# 8Bit-audio-7524-axelb-v2.net
KiCad netlist of a schematic drawn in EAGLE
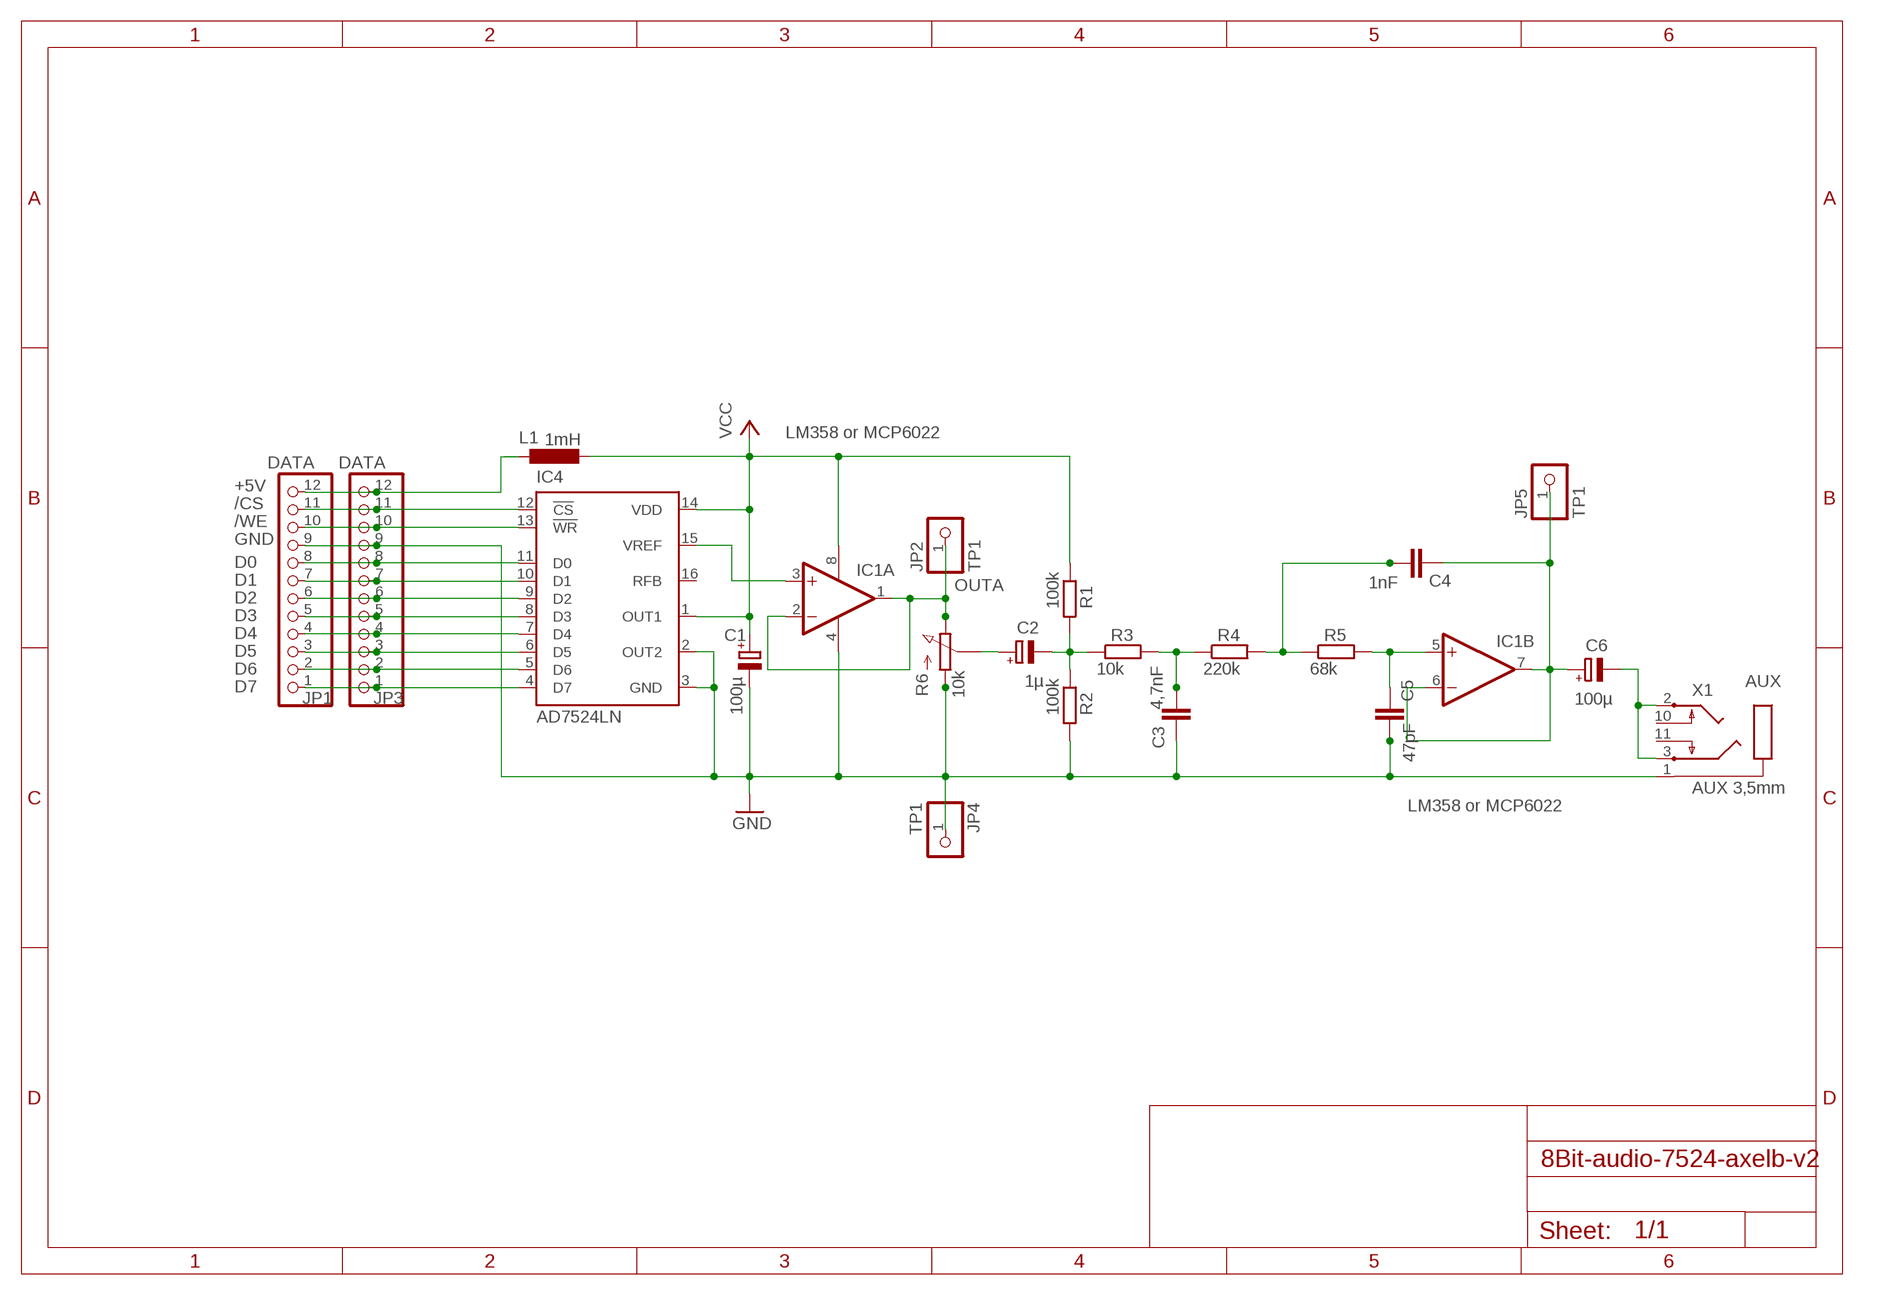
[diagram p0: schematic, sheet 1]

(export (version "E")
  (design (tool "Eeschema 10.0.6"))
  (components
    (comp (ref "C1")
      (value "100µ")
      (footprint "eagle-import:E5-5")
      (libsource (lib "eagle-import") (part "CPOL-EUE5-5"))
    )
    (comp (ref "C2")
      (value "1µ")
      (footprint "eagle-import:E5-5")
      (libsource (lib "eagle-import") (part "CPOL-EUE5-5"))
    )
    (comp (ref "C3")
      (value "4,7nF")
      (footprint "eagle-import:RCL_C025_050-055X075")
      (libsource (lib "eagle-import") (part "RCL_C-EU025_050-055X075"))
    )
    (comp (ref "C4")
      (value "1nF")
      (footprint "eagle-import:RCL_C025_050-055X075")
      (libsource (lib "eagle-import") (part "RCL_C-EU025_050-055X075"))
    )
    (comp (ref "C5")
      (value "47pF")
      (footprint "eagle-import:RCL_C025_050-055X075")
      (libsource (lib "eagle-import") (part "RCL_C-EU025_050-055X075"))
    )
    (comp (ref "C6")
      (value "100µ")
      (footprint "eagle-import:E5-5")
      (libsource (lib "eagle-import") (part "CPOL-EUE5-5"))
    )
    (comp (ref "IC1")
      (value "LM358 or MCP6022")
      (footprint "eagle-import:DIL08")
      (libsource (lib "eagle-import") (part "LM358N"))
    )
    (comp (ref "IC4")
      (value "AD7524LN")
      (footprint "eagle-import:DIL16")
      (fields (field (name "MF") "ALTERA CORPORATION") (field (name "MPN") "AD7524LNZ"))
      (libsource (lib "eagle-import") (part "AD7524NL"))
    )
    (comp (ref "JP1")
      (value "DATA")
      (footprint "eagle-import:1X12")
      (libsource (lib "eagle-import") (part "PINHD-1X12"))
    )
    (comp (ref "JP2")
      (value "TP1")
      (footprint "eagle-import:1X01")
      (libsource (lib "eagle-import") (part "PINHD-1X1"))
    )
    (comp (ref "JP3")
      (value "DATA")
      (footprint "eagle-import:1X12")
      (libsource (lib "eagle-import") (part "PINHD-1X12"))
    )
    (comp (ref "JP4")
      (value "TP1")
      (footprint "eagle-import:1X01")
      (libsource (lib "eagle-import") (part "PINHD-1X1"))
    )
    (comp (ref "JP5")
      (value "TP1")
      (footprint "eagle-import:1X01")
      (libsource (lib "eagle-import") (part "PINHD-1X1"))
    )
    (comp (ref "L1")
      (value "1mH")
      (footprint "eagle-import:0207_10")
      (libsource (lib "eagle-import") (part "L-EU0207/10"))
    )
    (comp (ref "R1")
      (value "100k")
      (footprint "eagle-import:0207_10")
      (libsource (lib "eagle-import") (part "R-EU_0207/10"))
    )
    (comp (ref "R2")
      (value "100k")
      (footprint "eagle-import:0207_10")
      (libsource (lib "eagle-import") (part "R-EU_0207/10"))
    )
    (comp (ref "R3")
      (value "10k")
      (footprint "eagle-import:0207_10")
      (libsource (lib "eagle-import") (part "R-EU_0207/10"))
    )
    (comp (ref "R4")
      (value "220k")
      (footprint "eagle-import:0207_10")
      (libsource (lib "eagle-import") (part "R-EU_0207/10"))
    )
    (comp (ref "R5")
      (value "68k")
      (footprint "eagle-import:0207_10")
      (libsource (lib "eagle-import") (part "R-EU_0207/10"))
    )
    (comp (ref "R6")
      (value "10k")
      (footprint "eagle-import:POT_3RP_1610N")
      (libsource (lib "eagle-import") (part "POT_3RP/1610N"))
    )
    (comp (ref "X1")
      (value "AUX 3,5mm")
      (footprint "eagle-import:SJ1-352XN")
      (libsource (lib "eagle-import") (part "CON-SJ1-352XNSJ1-352XN"))
    )
  )
  (nets
    (net (code "1") (name "/+5V") (class "Default")
      (node (ref "JP1") (pin "12") (pinfunction "12_12") (pintype "passive"))
      (node (ref "JP3") (pin "12") (pinfunction "12_12") (pintype "passive"))
      (node (ref "L1") (pin "1") (pinfunction "1_1") (pintype "passive"))
    )
    (net (code "2") (name "/AUX") (class "Default")
      (node (ref "C6") (pin "-") (pinfunction "-_-") (pintype "passive"))
      (node (ref "X1") (pin "2") (pinfunction "2_2") (pintype "passive"))
      (node (ref "X1") (pin "3") (pinfunction "3_3") (pintype "passive"))
    )
    (net (code "3") (name "/D0") (class "Default")
      (node (ref "IC4") (pin "11") (pinfunction "D0_11") (pintype "input"))
      (node (ref "JP1") (pin "8") (pinfunction "8_8") (pintype "passive"))
      (node (ref "JP3") (pin "8") (pinfunction "8_8") (pintype "passive"))
    )
    (net (code "4") (name "/D1") (class "Default")
      (node (ref "IC4") (pin "10") (pinfunction "D1_10") (pintype "input"))
      (node (ref "JP1") (pin "7") (pinfunction "7_7") (pintype "passive"))
      (node (ref "JP3") (pin "7") (pinfunction "7_7") (pintype "passive"))
    )
    (net (code "5") (name "/D2") (class "Default")
      (node (ref "IC4") (pin "9") (pinfunction "D2_9") (pintype "input"))
      (node (ref "JP1") (pin "6") (pinfunction "6_6") (pintype "passive"))
      (node (ref "JP3") (pin "6") (pinfunction "6_6") (pintype "passive"))
    )
    (net (code "6") (name "/D3") (class "Default")
      (node (ref "IC4") (pin "8") (pinfunction "D3_8") (pintype "input"))
      (node (ref "JP1") (pin "5") (pinfunction "5_5") (pintype "passive"))
      (node (ref "JP3") (pin "5") (pinfunction "5_5") (pintype "passive"))
    )
    (net (code "7") (name "/D4") (class "Default")
      (node (ref "IC4") (pin "7") (pinfunction "D4_7") (pintype "input"))
      (node (ref "JP1") (pin "4") (pinfunction "4_4") (pintype "passive"))
      (node (ref "JP3") (pin "4") (pinfunction "4_4") (pintype "passive"))
    )
    (net (code "8") (name "/D5") (class "Default")
      (node (ref "IC4") (pin "6") (pinfunction "D5_6") (pintype "input"))
      (node (ref "JP1") (pin "3") (pinfunction "3_3") (pintype "passive"))
      (node (ref "JP3") (pin "3") (pinfunction "3_3") (pintype "passive"))
    )
    (net (code "9") (name "/D6") (class "Default")
      (node (ref "IC4") (pin "5") (pinfunction "D6_5") (pintype "input"))
      (node (ref "JP1") (pin "2") (pinfunction "2_2") (pintype "passive"))
      (node (ref "JP3") (pin "2") (pinfunction "2_2") (pintype "passive"))
    )
    (net (code "10") (name "/D7") (class "Default")
      (node (ref "IC4") (pin "4") (pinfunction "D7_4") (pintype "input"))
      (node (ref "JP1") (pin "1") (pinfunction "1_1") (pintype "passive"))
      (node (ref "JP3") (pin "1") (pinfunction "1_1") (pintype "passive"))
    )
    (net (code "11") (name "/OUTA") (class "Default")
      (node (ref "IC1") (pin "1") (pinfunction "OUT_1") (pintype "output"))
      (node (ref "IC1") (pin "2") (pinfunction "-IN_2") (pintype "input"))
      (node (ref "JP2") (pin "1") (pinfunction "1_1") (pintype "passive"))
      (node (ref "R6") (pin "E1") (pinfunction "E1_E1") (pintype "passive"))
      (node (ref "R6") (pin "E2") (pinfunction "E2_E2") (pintype "passive"))
    )
    (net (code "12") (name "/{slash}CS") (class "Default")
      (node (ref "IC4") (pin "12") (pinfunction "~{CS}_12") (pintype "input"))
      (node (ref "JP1") (pin "11") (pinfunction "11_11") (pintype "passive"))
      (node (ref "JP3") (pin "11") (pinfunction "11_11") (pintype "passive"))
    )
    (net (code "13") (name "/{slash}WE") (class "Default")
      (node (ref "IC4") (pin "13") (pinfunction "~{WR}_13") (pintype "input"))
      (node (ref "JP1") (pin "10") (pinfunction "10_10") (pintype "passive"))
      (node (ref "JP3") (pin "10") (pinfunction "10_10") (pintype "passive"))
    )
    (net (code "14") (name "GND") (class "Default")
      (node (ref "C1") (pin "-") (pinfunction "-_-") (pintype "passive"))
      (node (ref "C3") (pin "1") (pinfunction "A1_1") (pintype "passive"))
      (node (ref "C5") (pin "2") (pinfunction "B1_2") (pintype "passive"))
      (node (ref "C5") (pin "3") (pinfunction "B2_3") (pintype "passive"))
      (node (ref "IC1") (pin "4") (pinfunction "V-_4") (pintype "power_in"))
      (node (ref "IC4") (pin "2") (pinfunction "OUT2_2") (pintype "passive"))
      (node (ref "IC4") (pin "3") (pinfunction "GND_3") (pintype "power_in"))
      (node (ref "JP1") (pin "9") (pinfunction "9_9") (pintype "passive"))
      (node (ref "JP3") (pin "9") (pinfunction "9_9") (pintype "passive"))
      (node (ref "JP4") (pin "1") (pinfunction "1_1") (pintype "passive"))
      (node (ref "R2") (pin "2") (pinfunction "2_2") (pintype "passive"))
      (node (ref "R6") (pin "A1") (pinfunction "A1_A1") (pintype "passive"))
      (node (ref "R6") (pin "A2") (pinfunction "A2_A2") (pintype "passive"))
      (node (ref "X1") (pin "1") (pinfunction "1_1") (pintype "passive"))
    )
    (net (code "15") (name "Net-(C2-Pad-)") (class "Default")
      (node (ref "C2") (pin "-") (pinfunction "-_-") (pintype "passive"))
      (node (ref "R1") (pin "2") (pinfunction "2_2") (pintype "passive"))
      (node (ref "R2") (pin "1") (pinfunction "1_1") (pintype "passive"))
      (node (ref "R3") (pin "1") (pinfunction "1_1") (pintype "passive"))
    )
    (net (code "16") (name "Net-(C3-B1)") (class "Default")
      (node (ref "C3") (pin "2") (pinfunction "B1_2") (pintype "passive"))
      (node (ref "C3") (pin "3") (pinfunction "B2_3") (pintype "passive"))
      (node (ref "R3") (pin "2") (pinfunction "2_2") (pintype "passive"))
      (node (ref "R4") (pin "1") (pinfunction "1_1") (pintype "passive"))
    )
    (net (code "17") (name "Net-(C4-A1)") (class "Default")
      (node (ref "C4") (pin "1") (pinfunction "A1_1") (pintype "passive"))
      (node (ref "C6") (pin "+") (pinfunction "+_+") (pintype "passive"))
      (node (ref "IC1") (pin "6") (pinfunction "-IN_6") (pintype "input"))
      (node (ref "IC1") (pin "7") (pinfunction "OUT_7") (pintype "output"))
      (node (ref "JP5") (pin "1") (pinfunction "1_1") (pintype "passive"))
    )
    (net (code "18") (name "Net-(C4-B1)") (class "Default")
      (node (ref "C4") (pin "2") (pinfunction "B1_2") (pintype "passive"))
      (node (ref "C4") (pin "3") (pinfunction "B2_3") (pintype "passive"))
      (node (ref "R4") (pin "2") (pinfunction "2_2") (pintype "passive"))
      (node (ref "R5") (pin "1") (pinfunction "1_1") (pintype "passive"))
    )
    (net (code "19") (name "Net-(C5-A1)") (class "Default")
      (node (ref "C5") (pin "1") (pinfunction "A1_1") (pintype "passive"))
      (node (ref "IC1") (pin "5") (pinfunction "+IN_5") (pintype "input"))
      (node (ref "R5") (pin "2") (pinfunction "2_2") (pintype "passive"))
    )
    (net (code "20") (name "Net-(IC1A-+IN)") (class "Default")
      (node (ref "IC1") (pin "3") (pinfunction "+IN_3") (pintype "input"))
      (node (ref "IC4") (pin "15") (pinfunction "VREF_15") (pintype "input"))
    )
    (net (code "21") (name "Net-(R6-S)") (class "Default")
      (node (ref "C2") (pin "+") (pinfunction "+_+") (pintype "passive"))
      (node (ref "R6") (pin "M") (pinfunction "S_M") (pintype "passive"))
    )
    (net (code "22") (name "VCC") (class "Default")
      (node (ref "C1") (pin "+") (pinfunction "+_+") (pintype "passive"))
      (node (ref "IC1") (pin "8") (pinfunction "V+_8") (pintype "power_in"))
      (node (ref "IC4") (pin "1") (pinfunction "OUT1_1") (pintype "passive"))
      (node (ref "IC4") (pin "14") (pinfunction "VDD_14") (pintype "power_in"))
      (node (ref "L1") (pin "2") (pinfunction "2_2") (pintype "passive"))
      (node (ref "R1") (pin "1") (pinfunction "1_1") (pintype "passive"))
    )
    (net (code "23") (name "unconnected-(IC4-RFB-Pad16)") (class "Default")
      (node (ref "IC4") (pin "16") (pinfunction "RFB_16") (pintype "passive"))
    )
    (net (code "24") (name "unconnected-(X1-Pad10)") (class "Default")
      (node (ref "X1") (pin "10") (pinfunction "10_10") (pintype "passive"))
    )
    (net (code "25") (name "unconnected-(X1-Pad11)") (class "Default")
      (node (ref "X1") (pin "11") (pinfunction "11_11") (pintype "passive"))
    )
  )
)
